# espoled.net
KiCad netlist of a schematic drawn in EAGLE
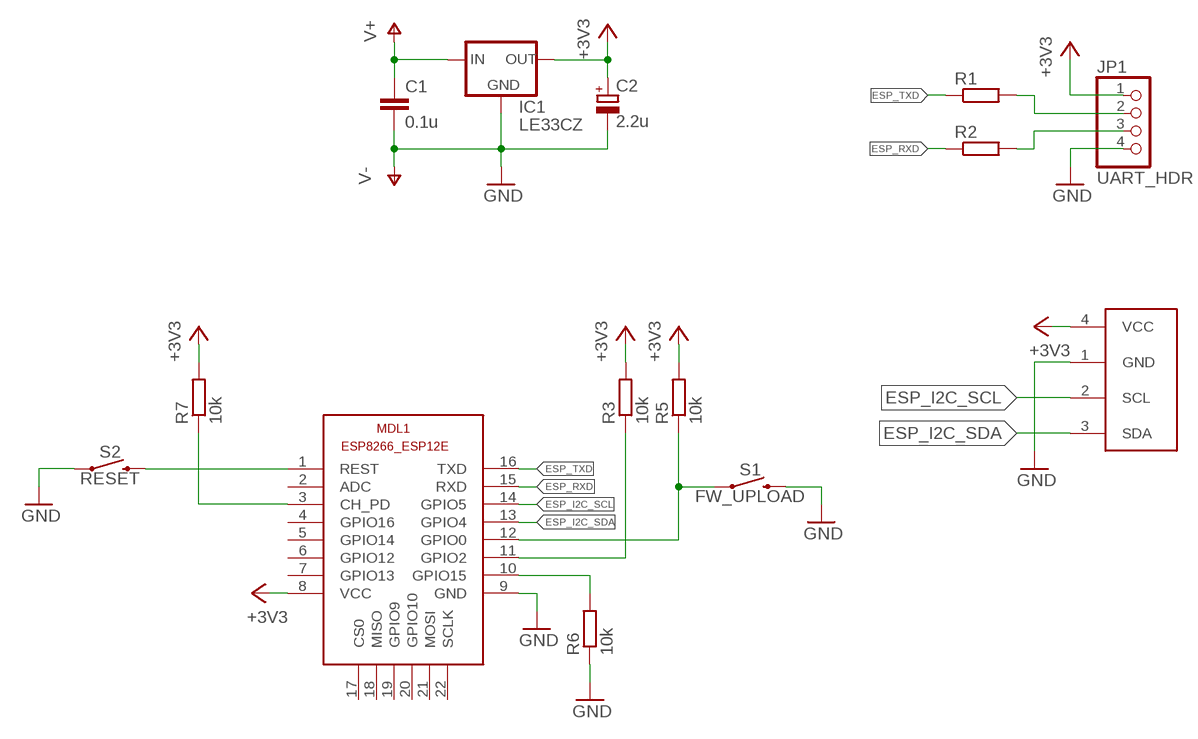
[diagram p0: schematic, sheet 1]

(export (version "E")
  (design (tool "Eeschema 10.0.6"))
  (components
    (comp (ref "C1")
      (value "0.1u")
      (footprint "eagle-import:C025-024X044")
      (libsource (lib "eagle-import") (part "C-EU025-024X044"))
    )
    (comp (ref "C2")
      (value "2.2u")
      (footprint "eagle-import:E2,5-5")
      (libsource (lib "eagle-import") (part "CPOL-EUE2.5-5"))
    )
    (comp (ref "IC1")
      (value "LE33CZ")
      (footprint "eagle-import:TO92")
      (libsource (lib "eagle-import") (part "LEXX_TO92"))
    )
    (comp (ref "JP1")
      (value "UART_HDR")
      (footprint "eagle-import:1X04")
      (libsource (lib "eagle-import") (part "PINHD-1X4"))
    )
    (comp (ref "MDL1")
      (value "ESP8266-12EESP8266-ESP12E")
      (footprint "eagle-import:ESP8266-ESP12E")
      (libsource (lib "eagle-import") (part "ESP8266-12EESP8266-ESP12E"))
    )
    (comp (ref "OLED")
      (value "I2C_OLED")
      (footprint "eagle-import:I2C_OLED_PACKAGE")
      (libsource (lib "eagle-import") (part "I2C_OLED"))
    )
    (comp (ref "R1")
      (value "R-EU_0204/5")
      (footprint "eagle-import:0204_5")
      (libsource (lib "eagle-import") (part "R-EU_0204/5"))
    )
    (comp (ref "R2")
      (value "R-EU_0204/5")
      (footprint "eagle-import:0204_5")
      (libsource (lib "eagle-import") (part "R-EU_0204/5"))
    )
    (comp (ref "R3")
      (value "10k")
      (footprint "eagle-import:0204_5")
      (libsource (lib "eagle-import") (part "R-EU_0204/5"))
    )
    (comp (ref "R5")
      (value "10k")
      (footprint "eagle-import:0204_5")
      (libsource (lib "eagle-import") (part "R-EU_0204/5"))
    )
    (comp (ref "R6")
      (value "10k")
      (footprint "eagle-import:0204_5")
      (libsource (lib "eagle-import") (part "R-EU_0204/5"))
    )
    (comp (ref "R7")
      (value "10k")
      (footprint "eagle-import:0204_5")
      (libsource (lib "eagle-import") (part "R-EU_0204/5"))
    )
    (comp (ref "S1")
      (value "FW_UPLOAD")
      (footprint "eagle-import:TACTILE_SWITCH_PTH_6.0MM")
      (libsource (lib "eagle-import") (part "MOMENTARY-SWITCH-SPST-PTH-6.0MM"))
    )
    (comp (ref "S2")
      (value "RESET")
      (footprint "eagle-import:TACTILE_SWITCH_PTH_6.0MM")
      (libsource (lib "eagle-import") (part "MOMENTARY-SWITCH-SPST-PTH-6.0MM"))
    )
  )
  (nets
    (net (code "1") (name "+3V3") (class "Default")
      (node (ref "C2") (pin "+") (pinfunction "+_+") (pintype "passive"))
      (node (ref "IC1") (pin "OUT") (pinfunction "OUT_OUT") (pintype "passive"))
      (node (ref "JP1") (pin "1") (pinfunction "1_1") (pintype "passive"))
      (node (ref "MDL1") (pin "8") (pinfunction "VCC_8") (pintype "bidirectional"))
      (node (ref "OLED") (pin "4") (pinfunction "VCC_4") (pintype "bidirectional"))
      (node (ref "R3") (pin "2") (pinfunction "2_2") (pintype "passive"))
      (node (ref "R5") (pin "2") (pinfunction "2_2") (pintype "passive"))
      (node (ref "R7") (pin "2") (pinfunction "2_2") (pintype "passive"))
    )
    (net (code "2") (name "ESP_I2C_SCL") (class "Default")
      (node (ref "MDL1") (pin "14") (pinfunction "GPIO5_14") (pintype "bidirectional"))
      (node (ref "OLED") (pin "2") (pinfunction "SCL_2") (pintype "bidirectional"))
    )
    (net (code "3") (name "ESP_I2C_SDA") (class "Default")
      (node (ref "MDL1") (pin "13") (pinfunction "GPIO4_13") (pintype "bidirectional"))
      (node (ref "OLED") (pin "3") (pinfunction "SDA_3") (pintype "bidirectional"))
    )
    (net (code "4") (name "ESP_RXD") (class "Default")
      (node (ref "MDL1") (pin "15") (pinfunction "RXD_15") (pintype "bidirectional"))
      (node (ref "R2") (pin "1") (pinfunction "1_1") (pintype "passive"))
    )
    (net (code "5") (name "ESP_TXD") (class "Default")
      (node (ref "MDL1") (pin "16") (pinfunction "TXD_16") (pintype "bidirectional"))
      (node (ref "R1") (pin "1") (pinfunction "1_1") (pintype "passive"))
    )
    (net (code "6") (name "GND") (class "Default")
      (node (ref "C1") (pin "2") (pinfunction "2_2") (pintype "passive"))
      (node (ref "C2") (pin "-") (pinfunction "-_-") (pintype "passive"))
      (node (ref "IC1") (pin "GND") (pinfunction "GND_GND") (pintype "input"))
      (node (ref "JP1") (pin "4") (pinfunction "4_4") (pintype "passive"))
      (node (ref "MDL1") (pin "9") (pinfunction "GND_9") (pintype "bidirectional"))
      (node (ref "OLED") (pin "1") (pinfunction "GND_1") (pintype "bidirectional"))
      (node (ref "R6") (pin "1") (pinfunction "1_1") (pintype "passive"))
      (node (ref "S1") (pin "3") (pinfunction "2_3") (pintype "passive"))
      (node (ref "S2") (pin "1") (pinfunction "1_1") (pintype "passive"))
    )
    (net (code "7") (name "Net-(JP1-Pad2)") (class "Default")
      (node (ref "JP1") (pin "2") (pinfunction "2_2") (pintype "passive"))
      (node (ref "R1") (pin "2") (pinfunction "2_2") (pintype "passive"))
    )
    (net (code "8") (name "Net-(JP1-Pad3)") (class "Default")
      (node (ref "JP1") (pin "3") (pinfunction "3_3") (pintype "passive"))
      (node (ref "R2") (pin "2") (pinfunction "2_2") (pintype "passive"))
    )
    (net (code "9") (name "Net-(MDL1-CH_PD)") (class "Default")
      (node (ref "MDL1") (pin "3") (pinfunction "CH_PD_3") (pintype "bidirectional"))
      (node (ref "R7") (pin "1") (pinfunction "1_1") (pintype "passive"))
    )
    (net (code "10") (name "Net-(MDL1-GPIO0)") (class "Default")
      (node (ref "MDL1") (pin "12") (pinfunction "GPIO0_12") (pintype "bidirectional"))
      (node (ref "R5") (pin "1") (pinfunction "1_1") (pintype "passive"))
      (node (ref "S1") (pin "1") (pinfunction "1_1") (pintype "passive"))
    )
    (net (code "11") (name "Net-(MDL1-GPIO2)") (class "Default")
      (node (ref "MDL1") (pin "11") (pinfunction "GPIO2_11") (pintype "bidirectional"))
      (node (ref "R3") (pin "1") (pinfunction "1_1") (pintype "passive"))
    )
    (net (code "12") (name "Net-(MDL1-GPIO15)") (class "Default")
      (node (ref "MDL1") (pin "10") (pinfunction "GPIO15_10") (pintype "bidirectional"))
      (node (ref "R6") (pin "2") (pinfunction "2_2") (pintype "passive"))
    )
    (net (code "13") (name "Net-(MDL1-REST)") (class "Default")
      (node (ref "MDL1") (pin "1") (pinfunction "REST_1") (pintype "bidirectional"))
      (node (ref "S2") (pin "3") (pinfunction "2_3") (pintype "passive"))
    )
    (net (code "14") (name "V+") (class "Default")
      (node (ref "C1") (pin "1") (pinfunction "1_1") (pintype "passive"))
      (node (ref "IC1") (pin "IN") (pinfunction "IN_IN") (pintype "input"))
    )
    (net (code "15") (name "unconnected-(MDL1-ADC-Pad2)") (class "Default")
      (node (ref "MDL1") (pin "2") (pinfunction "ADC_2") (pintype "bidirectional"))
    )
    (net (code "16") (name "unconnected-(MDL1-CS0-Pad17)") (class "Default")
      (node (ref "MDL1") (pin "17") (pinfunction "CS0_17") (pintype "bidirectional"))
    )
    (net (code "17") (name "unconnected-(MDL1-GPIO9-Pad19)") (class "Default")
      (node (ref "MDL1") (pin "19") (pinfunction "GPIO9_19") (pintype "bidirectional"))
    )
    (net (code "18") (name "unconnected-(MDL1-GPIO10-Pad20)") (class "Default")
      (node (ref "MDL1") (pin "20") (pinfunction "GPIO10_20") (pintype "bidirectional"))
    )
    (net (code "19") (name "unconnected-(MDL1-GPIO12-Pad6)") (class "Default")
      (node (ref "MDL1") (pin "6") (pinfunction "GPIO12_6") (pintype "bidirectional"))
    )
    (net (code "20") (name "unconnected-(MDL1-GPIO13-Pad7)") (class "Default")
      (node (ref "MDL1") (pin "7") (pinfunction "GPIO13_7") (pintype "bidirectional"))
    )
    (net (code "21") (name "unconnected-(MDL1-GPIO14-Pad5)") (class "Default")
      (node (ref "MDL1") (pin "5") (pinfunction "GPIO14_5") (pintype "bidirectional"))
    )
    (net (code "22") (name "unconnected-(MDL1-GPIO16-Pad4)") (class "Default")
      (node (ref "MDL1") (pin "4") (pinfunction "GPIO16_4") (pintype "bidirectional"))
    )
    (net (code "23") (name "unconnected-(MDL1-MISO-Pad18)") (class "Default")
      (node (ref "MDL1") (pin "18") (pinfunction "MISO_18") (pintype "bidirectional"))
    )
    (net (code "24") (name "unconnected-(MDL1-MOSI-Pad21)") (class "Default")
      (node (ref "MDL1") (pin "21") (pinfunction "MOSI_21") (pintype "bidirectional"))
    )
    (net (code "25") (name "unconnected-(MDL1-SCLK-Pad22)") (class "Default")
      (node (ref "MDL1") (pin "22") (pinfunction "SCLK_22") (pintype "bidirectional"))
    )
  )
)
